# Solenoise_v6.net
KiCad netlist of a schematic drawn in EAGLE
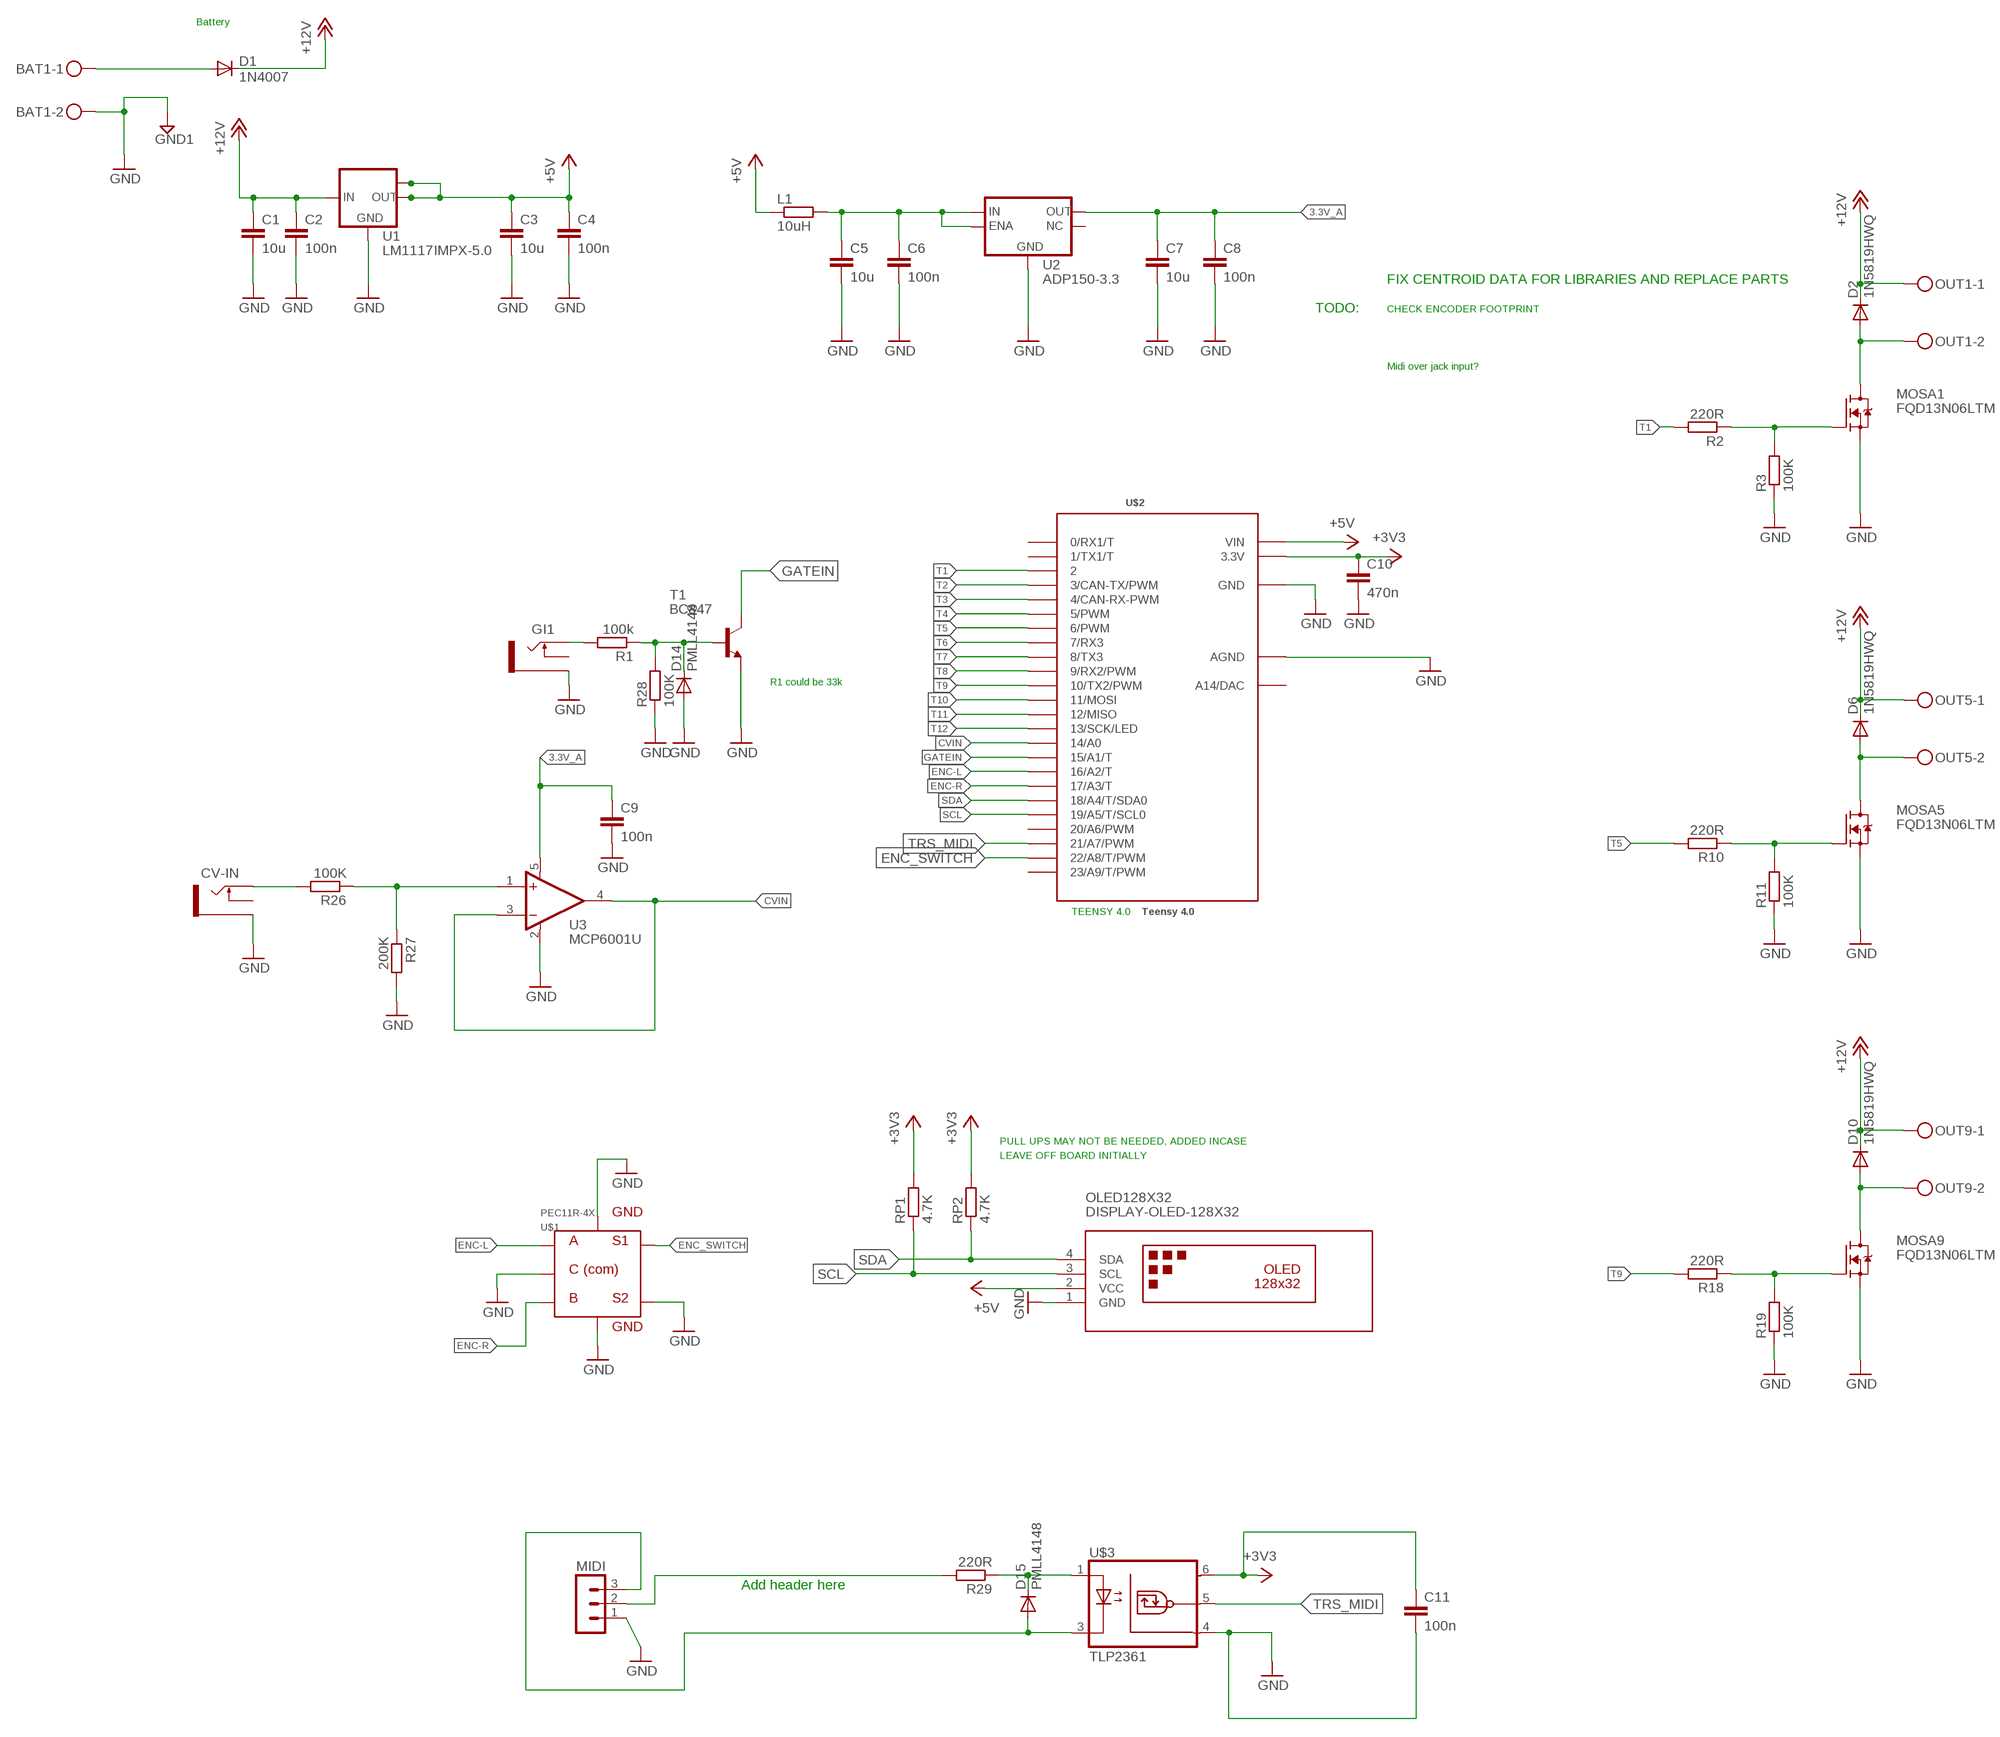
[diagram p0: schematic, sheet 1, part 1 of 2]
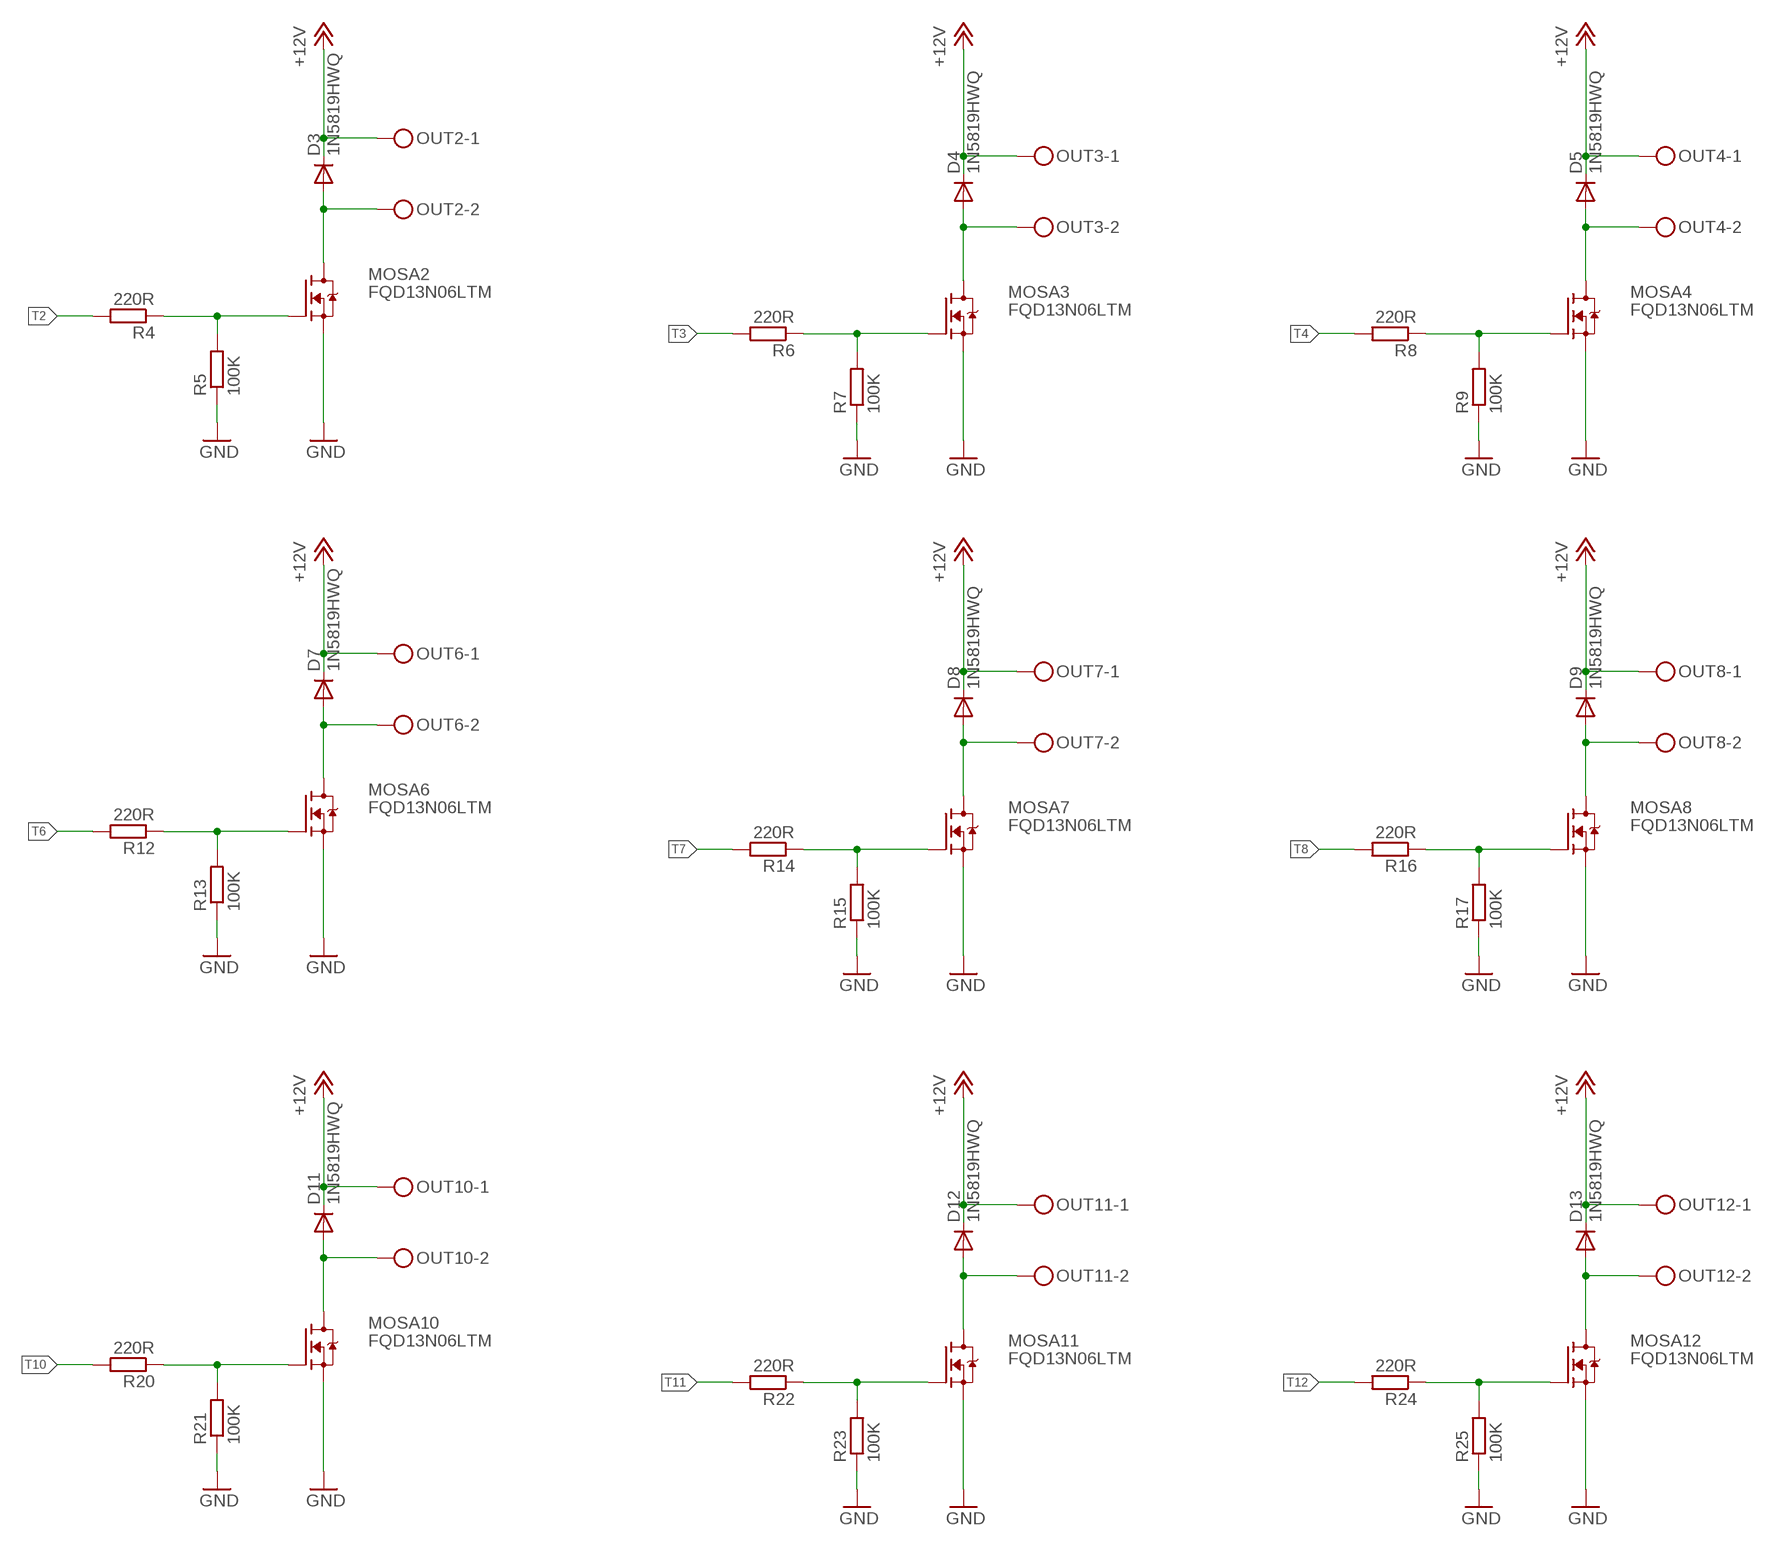
[diagram p1: schematic, sheet 1, part 2 of 2]

(export (version "E")
  (design (tool "Eeschema 10.0.6"))
  (components
    (comp (ref "BAT1")
      (value "MKDSN1,5/2-5,08")
      (footprint "eagle-import:MKDSN1,5_2-5,08")
      (fields (field (name "MPN") "MKDSN 1,5/2-5.08"))
      (libsource (lib "eagle-import") (part "MKDSN1,5/2-5,08"))
    )
    (comp (ref "C1")
      (value "10u")
      (footprint "eagle-import:C1206")
      (libsource (lib "eagle-import") (part "C-EUC1206"))
    )
    (comp (ref "C2")
      (value "100n")
      (footprint "eagle-import:C0805")
      (libsource (lib "eagle-import") (part "C-EUC0805"))
    )
    (comp (ref "C3")
      (value "10u")
      (footprint "eagle-import:C1206")
      (libsource (lib "eagle-import") (part "C-EUC1206"))
    )
    (comp (ref "C4")
      (value "100n")
      (footprint "eagle-import:C0805")
      (libsource (lib "eagle-import") (part "C-EUC0805"))
    )
    (comp (ref "C5")
      (value "10u")
      (footprint "eagle-import:C1206")
      (libsource (lib "eagle-import") (part "C-EUC1206"))
    )
    (comp (ref "C6")
      (value "100n")
      (footprint "eagle-import:C0805")
      (libsource (lib "eagle-import") (part "C-EUC0805"))
    )
    (comp (ref "C7")
      (value "10u")
      (footprint "eagle-import:C1206")
      (libsource (lib "eagle-import") (part "C-EUC1206"))
    )
    (comp (ref "C8")
      (value "100n")
      (footprint "eagle-import:C0805")
      (libsource (lib "eagle-import") (part "C-EUC0805"))
    )
    (comp (ref "C9")
      (value "100n")
      (footprint "eagle-import:C0805")
      (libsource (lib "eagle-import") (part "C-EUC0805"))
    )
    (comp (ref "C10")
      (value "470n")
      (footprint "eagle-import:C0805")
      (libsource (lib "eagle-import") (part "C-EUC0805"))
    )
    (comp (ref "C11")
      (value "100n")
      (footprint "eagle-import:C0805")
      (libsource (lib "eagle-import") (part "C-EUC0805"))
    )
    (comp (ref "CV-IN")
      (value "THONKICONNNEW")
      (footprint "eagle-import:WQP-PJ301M-12_JACK")
      (libsource (lib "eagle-import") (part "THONKICONNNEW"))
    )
    (comp (ref "D1")
      (value "1N4007")
      (footprint "eagle-import:DO41-10")
      (libsource (lib "eagle-import") (part "1N4004"))
    )
    (comp (ref "D2")
      (value "1N5819HWQ")
      (footprint "eagle-import:SOD123")
      (libsource (lib "eagle-import") (part "MBR0520LT"))
    )
    (comp (ref "D3")
      (value "1N5819HWQ")
      (footprint "eagle-import:SOD123")
      (libsource (lib "eagle-import") (part "MBR0520LT"))
    )
    (comp (ref "D4")
      (value "1N5819HWQ")
      (footprint "eagle-import:SOD123")
      (libsource (lib "eagle-import") (part "MBR0520LT"))
    )
    (comp (ref "D5")
      (value "1N5819HWQ")
      (footprint "eagle-import:SOD123")
      (libsource (lib "eagle-import") (part "MBR0520LT"))
    )
    (comp (ref "D6")
      (value "1N5819HWQ")
      (footprint "eagle-import:SOD123")
      (libsource (lib "eagle-import") (part "MBR0520LT"))
    )
    (comp (ref "D7")
      (value "1N5819HWQ")
      (footprint "eagle-import:SOD123")
      (libsource (lib "eagle-import") (part "MBR0520LT"))
    )
    (comp (ref "D8")
      (value "1N5819HWQ")
      (footprint "eagle-import:SOD123")
      (libsource (lib "eagle-import") (part "MBR0520LT"))
    )
    (comp (ref "D9")
      (value "1N5819HWQ")
      (footprint "eagle-import:SOD123")
      (libsource (lib "eagle-import") (part "MBR0520LT"))
    )
    (comp (ref "D10")
      (value "1N5819HWQ")
      (footprint "eagle-import:SOD123")
      (libsource (lib "eagle-import") (part "MBR0520LT"))
    )
    (comp (ref "D11")
      (value "1N5819HWQ")
      (footprint "eagle-import:SOD123")
      (libsource (lib "eagle-import") (part "MBR0520LT"))
    )
    (comp (ref "D12")
      (value "1N5819HWQ")
      (footprint "eagle-import:SOD123")
      (libsource (lib "eagle-import") (part "MBR0520LT"))
    )
    (comp (ref "D13")
      (value "1N5819HWQ")
      (footprint "eagle-import:SOD123")
      (libsource (lib "eagle-import") (part "MBR0520LT"))
    )
    (comp (ref "D14")
      (value "PMLL4148")
      (footprint "eagle-import:SOD80C")
      (libsource (lib "eagle-import") (part "PMLL4150"))
    )
    (comp (ref "D15")
      (value "PMLL4148")
      (footprint "eagle-import:SOD80C")
      (libsource (lib "eagle-import") (part "PMLL4150"))
    )
    (comp (ref "GI1")
      (value "THONKICONNNEW")
      (footprint "eagle-import:WQP-PJ301M-12_JACK")
      (libsource (lib "eagle-import") (part "THONKICONNNEW"))
    )
    (comp (ref "L1")
      (value "10uH")
      (footprint "eagle-import:R0805")
      (libsource (lib "eagle-import") (part "R-EU_R0805"))
    )
    (comp (ref "MIDI")
      (value "MA03-1")
      (footprint "eagle-import:MA03-1")
      (libsource (lib "eagle-import") (part "MA03-1"))
    )
    (comp (ref "MOSA1")
      (value "FQD13N06LTM")
      (footprint "eagle-import:FQD13N06LTM")
      (libsource (lib "eagle-import") (part "FQD13N06LTM"))
    )
    (comp (ref "MOSA2")
      (value "FQD13N06LTM")
      (footprint "eagle-import:FQD13N06LTM")
      (libsource (lib "eagle-import") (part "FQD13N06LTM"))
    )
    (comp (ref "MOSA3")
      (value "FQD13N06LTM")
      (footprint "eagle-import:FQD13N06LTM")
      (libsource (lib "eagle-import") (part "FQD13N06LTM"))
    )
    (comp (ref "MOSA4")
      (value "FQD13N06LTM")
      (footprint "eagle-import:FQD13N06LTM")
      (libsource (lib "eagle-import") (part "FQD13N06LTM"))
    )
    (comp (ref "MOSA5")
      (value "FQD13N06LTM")
      (footprint "eagle-import:FQD13N06LTM")
      (libsource (lib "eagle-import") (part "FQD13N06LTM"))
    )
    (comp (ref "MOSA6")
      (value "FQD13N06LTM")
      (footprint "eagle-import:FQD13N06LTM")
      (libsource (lib "eagle-import") (part "FQD13N06LTM"))
    )
    (comp (ref "MOSA7")
      (value "FQD13N06LTM")
      (footprint "eagle-import:FQD13N06LTM")
      (libsource (lib "eagle-import") (part "FQD13N06LTM"))
    )
    (comp (ref "MOSA8")
      (value "FQD13N06LTM")
      (footprint "eagle-import:FQD13N06LTM")
      (libsource (lib "eagle-import") (part "FQD13N06LTM"))
    )
    (comp (ref "MOSA9")
      (value "FQD13N06LTM")
      (footprint "eagle-import:FQD13N06LTM")
      (libsource (lib "eagle-import") (part "FQD13N06LTM"))
    )
    (comp (ref "MOSA10")
      (value "FQD13N06LTM")
      (footprint "eagle-import:FQD13N06LTM")
      (libsource (lib "eagle-import") (part "FQD13N06LTM"))
    )
    (comp (ref "MOSA11")
      (value "FQD13N06LTM")
      (footprint "eagle-import:FQD13N06LTM")
      (libsource (lib "eagle-import") (part "FQD13N06LTM"))
    )
    (comp (ref "MOSA12")
      (value "FQD13N06LTM")
      (footprint "eagle-import:FQD13N06LTM")
      (libsource (lib "eagle-import") (part "FQD13N06LTM"))
    )
    (comp (ref "OLED128X32")
      (value "DISPLAY-OLED-128X32")
      (footprint "eagle-import:DISPLAY-OLED-128X32")
      (libsource (lib "eagle-import") (part "DISPLAY-OLED-128X32"))
    )
    (comp (ref "OUT1")
      (value "MKDSN1,5/2-5,08")
      (footprint "eagle-import:MKDSN1,5_2-5,08")
      (fields (field (name "MPN") "MKDSN 1,5/2-5.08"))
      (libsource (lib "eagle-import") (part "MKDSN1,5/2-5,08"))
    )
    (comp (ref "OUT2")
      (value "MKDSN1,5/2-5,08")
      (footprint "eagle-import:MKDSN1,5_2-5,08")
      (fields (field (name "MPN") "MKDSN 1,5/2-5.08"))
      (libsource (lib "eagle-import") (part "MKDSN1,5/2-5,08"))
    )
    (comp (ref "OUT3")
      (value "MKDSN1,5/2-5,08")
      (footprint "eagle-import:MKDSN1,5_2-5,08")
      (fields (field (name "MPN") "MKDSN 1,5/2-5.08"))
      (libsource (lib "eagle-import") (part "MKDSN1,5/2-5,08"))
    )
    (comp (ref "OUT4")
      (value "MKDSN1,5/2-5,08")
      (footprint "eagle-import:MKDSN1,5_2-5,08")
      (fields (field (name "MPN") "MKDSN 1,5/2-5.08"))
      (libsource (lib "eagle-import") (part "MKDSN1,5/2-5,08"))
    )
    (comp (ref "OUT5")
      (value "MKDSN1,5/2-5,08")
      (footprint "eagle-import:MKDSN1,5_2-5,08")
      (fields (field (name "MPN") "MKDSN 1,5/2-5.08"))
      (libsource (lib "eagle-import") (part "MKDSN1,5/2-5,08"))
    )
    (comp (ref "OUT6")
      (value "MKDSN1,5/2-5,08")
      (footprint "eagle-import:MKDSN1,5_2-5,08")
      (fields (field (name "MPN") "MKDSN 1,5/2-5.08"))
      (libsource (lib "eagle-import") (part "MKDSN1,5/2-5,08"))
    )
    (comp (ref "OUT7")
      (value "MKDSN1,5/2-5,08")
      (footprint "eagle-import:MKDSN1,5_2-5,08")
      (fields (field (name "MPN") "MKDSN 1,5/2-5.08"))
      (libsource (lib "eagle-import") (part "MKDSN1,5/2-5,08"))
    )
    (comp (ref "OUT8")
      (value "MKDSN1,5/2-5,08")
      (footprint "eagle-import:MKDSN1,5_2-5,08")
      (fields (field (name "MPN") "MKDSN 1,5/2-5.08"))
      (libsource (lib "eagle-import") (part "MKDSN1,5/2-5,08"))
    )
    (comp (ref "OUT9")
      (value "MKDSN1,5/2-5,08")
      (footprint "eagle-import:MKDSN1,5_2-5,08")
      (fields (field (name "MPN") "MKDSN 1,5/2-5.08"))
      (libsource (lib "eagle-import") (part "MKDSN1,5/2-5,08"))
    )
    (comp (ref "OUT10")
      (value "MKDSN1,5/2-5,08")
      (footprint "eagle-import:MKDSN1,5_2-5,08")
      (fields (field (name "MPN") "MKDSN 1,5/2-5.08"))
      (libsource (lib "eagle-import") (part "MKDSN1,5/2-5,08"))
    )
    (comp (ref "OUT11")
      (value "MKDSN1,5/2-5,08")
      (footprint "eagle-import:MKDSN1,5_2-5,08")
      (fields (field (name "MPN") "MKDSN 1,5/2-5.08"))
      (libsource (lib "eagle-import") (part "MKDSN1,5/2-5,08"))
    )
    (comp (ref "OUT12")
      (value "MKDSN1,5/2-5,08")
      (footprint "eagle-import:MKDSN1,5_2-5,08")
      (fields (field (name "MPN") "MKDSN 1,5/2-5.08"))
      (libsource (lib "eagle-import") (part "MKDSN1,5/2-5,08"))
    )
    (comp (ref "R1")
      (value "100k")
      (footprint "eagle-import:R0805")
      (libsource (lib "eagle-import") (part "R-EU_R0805"))
    )
    (comp (ref "R2")
      (value "220R")
      (footprint "eagle-import:R0805")
      (libsource (lib "eagle-import") (part "R-EU_R0805"))
    )
    (comp (ref "R3")
      (value "100K")
      (footprint "eagle-import:R0805")
      (libsource (lib "eagle-import") (part "R-EU_R0805"))
    )
    (comp (ref "R4")
      (value "220R")
      (footprint "eagle-import:R0805")
      (libsource (lib "eagle-import") (part "R-EU_R0805"))
    )
    (comp (ref "R5")
      (value "100K")
      (footprint "eagle-import:R0805")
      (libsource (lib "eagle-import") (part "R-EU_R0805"))
    )
    (comp (ref "R6")
      (value "220R")
      (footprint "eagle-import:R0805")
      (libsource (lib "eagle-import") (part "R-EU_R0805"))
    )
    (comp (ref "R7")
      (value "100K")
      (footprint "eagle-import:R0805")
      (libsource (lib "eagle-import") (part "R-EU_R0805"))
    )
    (comp (ref "R8")
      (value "220R")
      (footprint "eagle-import:R0805")
      (libsource (lib "eagle-import") (part "R-EU_R0805"))
    )
    (comp (ref "R9")
      (value "100K")
      (footprint "eagle-import:R0805")
      (libsource (lib "eagle-import") (part "R-EU_R0805"))
    )
    (comp (ref "R10")
      (value "220R")
      (footprint "eagle-import:R0805")
      (libsource (lib "eagle-import") (part "R-EU_R0805"))
    )
    (comp (ref "R11")
      (value "100K")
      (footprint "eagle-import:R0805")
      (libsource (lib "eagle-import") (part "R-EU_R0805"))
    )
    (comp (ref "R12")
      (value "220R")
      (footprint "eagle-import:R0805")
      (libsource (lib "eagle-import") (part "R-EU_R0805"))
    )
    (comp (ref "R13")
      (value "100K")
      (footprint "eagle-import:R0805")
      (libsource (lib "eagle-import") (part "R-EU_R0805"))
    )
    (comp (ref "R14")
      (value "220R")
      (footprint "eagle-import:R0805")
      (libsource (lib "eagle-import") (part "R-EU_R0805"))
    )
    (comp (ref "R15")
      (value "100K")
      (footprint "eagle-import:R0805")
      (libsource (lib "eagle-import") (part "R-EU_R0805"))
    )
    (comp (ref "R16")
      (value "220R")
      (footprint "eagle-import:R0805")
      (libsource (lib "eagle-import") (part "R-EU_R0805"))
    )
    (comp (ref "R17")
      (value "100K")
      (footprint "eagle-import:R0805")
      (libsource (lib "eagle-import") (part "R-EU_R0805"))
    )
    (comp (ref "R18")
      (value "220R")
      (footprint "eagle-import:R0805")
      (libsource (lib "eagle-import") (part "R-EU_R0805"))
    )
    (comp (ref "R19")
      (value "100K")
      (footprint "eagle-import:R0805")
      (libsource (lib "eagle-import") (part "R-EU_R0805"))
    )
    (comp (ref "R20")
      (value "220R")
      (footprint "eagle-import:R0805")
      (libsource (lib "eagle-import") (part "R-EU_R0805"))
    )
    (comp (ref "R21")
      (value "100K")
      (footprint "eagle-import:R0805")
      (libsource (lib "eagle-import") (part "R-EU_R0805"))
    )
    (comp (ref "R22")
      (value "220R")
      (footprint "eagle-import:R0805")
      (libsource (lib "eagle-import") (part "R-EU_R0805"))
    )
    (comp (ref "R23")
      (value "100K")
      (footprint "eagle-import:R0805")
      (libsource (lib "eagle-import") (part "R-EU_R0805"))
    )
    (comp (ref "R24")
      (value "220R")
      (footprint "eagle-import:R0805")
      (libsource (lib "eagle-import") (part "R-EU_R0805"))
    )
    (comp (ref "R25")
      (value "100K")
      (footprint "eagle-import:R0805")
      (libsource (lib "eagle-import") (part "R-EU_R0805"))
    )
    (comp (ref "R26")
      (value "100K")
      (footprint "eagle-import:R0805")
      (libsource (lib "eagle-import") (part "R-EU_R0805"))
    )
    (comp (ref "R27")
      (value "200K")
      (footprint "eagle-import:R0805")
      (libsource (lib "eagle-import") (part "R-EU_R0805"))
    )
    (comp (ref "R28")
      (value "100K")
      (footprint "eagle-import:R0805")
      (libsource (lib "eagle-import") (part "R-EU_R0805"))
    )
    (comp (ref "R29")
      (value "220R")
      (footprint "eagle-import:R0805")
      (libsource (lib "eagle-import") (part "R-EU_R0805"))
    )
    (comp (ref "RP1")
      (value "4.7K")
      (footprint "eagle-import:R0805")
      (libsource (lib "eagle-import") (part "R-EU_R0805"))
    )
    (comp (ref "RP2")
      (value "4.7K")
      (footprint "eagle-import:R0805")
      (libsource (lib "eagle-import") (part "R-EU_R0805"))
    )
    (comp (ref "T1")
      (value "BC847")
      (footprint "eagle-import:SOT23")
      (libsource (lib "eagle-import") (part "BC847"))
    )
    (comp (ref "U$1")
      (value "PEC11R-4X")
      (footprint "eagle-import:ENC")
      (libsource (lib "eagle-import") (part "PEC11R-4X"))
    )
    (comp (ref "U$2")
      (value "Teensy 4.0")
      (footprint "eagle-import:TEENSY_3.1_DAC")
      (libsource (lib "eagle-import") (part "TEENSY_3.1_DAC"))
    )
    (comp (ref "U$3")
      (value "TLP2361")
      (footprint "eagle-import:TLP2361")
      (libsource (lib "eagle-import") (part "TLP2361"))
    )
    (comp (ref "U1")
      (value "LM1117IMPX-5.0")
      (footprint "eagle-import:SOT223")
      (libsource (lib "eagle-import") (part "LM1117IMPX-5.0"))
    )
    (comp (ref "U2")
      (value "ADP150-3.3")
      (footprint "eagle-import:SOT23-5")
      (libsource (lib "eagle-import") (part "ADP150-3.3"))
    )
    (comp (ref "U3")
      (value "MCP6001U")
      (footprint "eagle-import:MCP6001")
      (libsource (lib "eagle-import") (part "MCP6001U"))
    )
  )
  (nets
    (net (code "1") (name "+3V3") (class "Default")
      (node (ref "C10") (pin "1") (pinfunction "1_1") (pintype "passive"))
      (node (ref "C11") (pin "1") (pinfunction "1_1") (pintype "passive"))
      (node (ref "RP1") (pin "2") (pinfunction "2_2") (pintype "passive"))
      (node (ref "RP2") (pin "2") (pinfunction "2_2") (pintype "passive"))
      (node (ref "U$2") (pin "3.3V") (pinfunction "3.3V_3.3V") (pintype "power_in"))
      (node (ref "U$3") (pin "6") (pinfunction "VCC_6") (pintype "passive"))
    )
    (net (code "2") (name "+5V") (class "Default")
      (node (ref "C3") (pin "1") (pinfunction "1_1") (pintype "passive"))
      (node (ref "C4") (pin "1") (pinfunction "1_1") (pintype "passive"))
      (node (ref "L1") (pin "1") (pinfunction "1_1") (pintype "passive"))
      (node (ref "OLED128X32") (pin "2") (pinfunction "VCC_2") (pintype "power_in"))
      (node (ref "U$2") (pin "VIN") (pinfunction "VIN_VIN") (pintype "power_in"))
      (node (ref "U1") (pin "2") (pinfunction "OUT_2") (pintype "passive"))
      (node (ref "U1") (pin "TAB") (pinfunction "OUT1_TAB") (pintype "passive"))
    )
    (net (code "3") (name "+12V") (class "Default")
      (node (ref "C1") (pin "1") (pinfunction "1_1") (pintype "passive"))
      (node (ref "C2") (pin "1") (pinfunction "1_1") (pintype "passive"))
      (node (ref "D1") (pin "C") (pinfunction "C_C") (pintype "passive"))
      (node (ref "D10") (pin "C") (pinfunction "C_C") (pintype "passive"))
      (node (ref "D11") (pin "C") (pinfunction "C_C") (pintype "passive"))
      (node (ref "D12") (pin "C") (pinfunction "C_C") (pintype "passive"))
      (node (ref "D13") (pin "C") (pinfunction "C_C") (pintype "passive"))
      (node (ref "D2") (pin "C") (pinfunction "C_C") (pintype "passive"))
      (node (ref "D3") (pin "C") (pinfunction "C_C") (pintype "passive"))
      (node (ref "D4") (pin "C") (pinfunction "C_C") (pintype "passive"))
      (node (ref "D5") (pin "C") (pinfunction "C_C") (pintype "passive"))
      (node (ref "D6") (pin "C") (pinfunction "C_C") (pintype "passive"))
      (node (ref "D7") (pin "C") (pinfunction "C_C") (pintype "passive"))
      (node (ref "D8") (pin "C") (pinfunction "C_C") (pintype "passive"))
      (node (ref "D9") (pin "C") (pinfunction "C_C") (pintype "passive"))
      (node (ref "OUT1") (pin "1") (pinfunction "KL_1") (pintype "passive"))
      (node (ref "OUT10") (pin "1") (pinfunction "KL_1") (pintype "passive"))
      (node (ref "OUT11") (pin "1") (pinfunction "KL_1") (pintype "passive"))
      (node (ref "OUT12") (pin "1") (pinfunction "KL_1") (pintype "passive"))
      (node (ref "OUT2") (pin "1") (pinfunction "KL_1") (pintype "passive"))
      (node (ref "OUT3") (pin "1") (pinfunction "KL_1") (pintype "passive"))
      (node (ref "OUT4") (pin "1") (pinfunction "KL_1") (pintype "passive"))
      (node (ref "OUT5") (pin "1") (pinfunction "KL_1") (pintype "passive"))
      (node (ref "OUT6") (pin "1") (pinfunction "KL_1") (pintype "passive"))
      (node (ref "OUT7") (pin "1") (pinfunction "KL_1") (pintype "passive"))
      (node (ref "OUT8") (pin "1") (pinfunction "KL_1") (pintype "passive"))
      (node (ref "OUT9") (pin "1") (pinfunction "KL_1") (pintype "passive"))
      (node (ref "U1") (pin "3") (pinfunction "IN_3") (pintype "input"))
    )
    (net (code "4") (name "3.3V_A") (class "Default")
      (node (ref "C7") (pin "1") (pinfunction "1_1") (pintype "passive"))
      (node (ref "C8") (pin "1") (pinfunction "1_1") (pintype "passive"))
      (node (ref "C9") (pin "1") (pinfunction "1_1") (pintype "passive"))
      (node (ref "U2") (pin "OUT") (pinfunction "VOUT_OUT") (pintype "passive"))
      (node (ref "U3") (pin "5") (pinfunction "V+_5") (pintype "power_in"))
    )
    (net (code "5") (name "CVIN") (class "Default")
      (node (ref "U$2") (pin "14/A0") (pinfunction "14/A0_14/A0") (pintype "bidirectional"))
      (node (ref "U3") (pin "3") (pinfunction "-IN_3") (pintype "input"))
      (node (ref "U3") (pin "4") (pinfunction "OUT_4") (pintype "output"))
    )
    (net (code "6") (name "ENC-L") (class "Default")
      (node (ref "U$1") (pin "A") (pinfunction "A_A") (pintype "passive"))
      (node (ref "U$2") (pin "16/A2") (pinfunction "16/A2/T_16/A2") (pintype "bidirectional"))
    )
    (net (code "7") (name "ENC-R") (class "Default")
      (node (ref "U$1") (pin "B") (pinfunction "B_B") (pintype "passive"))
      (node (ref "U$2") (pin "17/A3") (pinfunction "17/A3/T_17/A3") (pintype "bidirectional"))
    )
    (net (code "8") (name "ENC_SWITCH") (class "Default")
      (node (ref "U$1") (pin "1") (pinfunction "SW1_1") (pintype "passive"))
      (node (ref "U$2") (pin "22/A8") (pinfunction "22/A8/T/PWM_22/A8") (pintype "bidirectional"))
    )
    (net (code "9") (name "GATEIN") (class "Default")
      (node (ref "T1") (pin "3") (pinfunction "C_3") (pintype "passive"))
      (node (ref "U$2") (pin "15/A1") (pinfunction "15/A1/T_15/A1") (pintype "bidirectional"))
    )
    (net (code "10") (name "GND") (class "Default")
      (node (ref "BAT1") (pin "2") (pinfunction "KL_2") (pintype "passive"))
      (node (ref "C1") (pin "2") (pinfunction "2_2") (pintype "passive"))
      (node (ref "C10") (pin "2") (pinfunction "2_2") (pintype "passive"))
      (node (ref "C11") (pin "2") (pinfunction "2_2") (pintype "passive"))
      (node (ref "C2") (pin "2") (pinfunction "2_2") (pintype "passive"))
      (node (ref "C3") (pin "2") (pinfunction "2_2") (pintype "passive"))
      (node (ref "C4") (pin "2") (pinfunction "2_2") (pintype "passive"))
      (node (ref "C5") (pin "2") (pinfunction "2_2") (pintype "passive"))
      (node (ref "C6") (pin "2") (pinfunction "2_2") (pintype "passive"))
      (node (ref "C7") (pin "2") (pinfunction "2_2") (pintype "passive"))
      (node (ref "C8") (pin "2") (pinfunction "2_2") (pintype "passive"))
      (node (ref "C9") (pin "2") (pinfunction "2_2") (pintype "passive"))
      (node (ref "CV-IN") (pin "P$3_SLEEVE") (pinfunction "SLEEVE_P$3_SLEEVE") (pintype "passive"))
      (node (ref "D14") (pin "A") (pinfunction "A_A") (pintype "passive"))
      (node (ref "GI1") (pin "P$3_SLEEVE") (pinfunction "SLEEVE_P$3_SLEEVE") (pintype "passive"))
      (node (ref "MIDI") (pin "1") (pinfunction "1_1") (pintype "passive"))
      (node (ref "MOSA1") (pin "2") (pinfunction "S_2") (pintype "passive"))
      (node (ref "MOSA10") (pin "2") (pinfunction "S_2") (pintype "passive"))
      (node (ref "MOSA11") (pin "2") (pinfunction "S_2") (pintype "passive"))
      (node (ref "MOSA12") (pin "2") (pinfunction "S_2") (pintype "passive"))
      (node (ref "MOSA2") (pin "2") (pinfunction "S_2") (pintype "passive"))
      (node (ref "MOSA3") (pin "2") (pinfunction "S_2") (pintype "passive"))
      (node (ref "MOSA4") (pin "2") (pinfunction "S_2") (pintype "passive"))
      (node (ref "MOSA5") (pin "2") (pinfunction "S_2") (pintype "passive"))
      (node (ref "MOSA6") (pin "2") (pinfunction "S_2") (pintype "passive"))
      (node (ref "MOSA7") (pin "2") (pinfunction "S_2") (pintype "passive"))
      (node (ref "MOSA8") (pin "2") (pinfunction "S_2") (pintype "passive"))
      (node (ref "MOSA9") (pin "2") (pinfunction "S_2") (pintype "passive"))
      (node (ref "OLED128X32") (pin "1") (pinfunction "GND_1") (pintype "power_in"))
      (node (ref "R11") (pin "1") (pinfunction "1_1") (pintype "passive"))
      (node (ref "R13") (pin "1") (pinfunction "1_1") (pintype "passive"))
      (node (ref "R15") (pin "1") (pinfunction "1_1") (pintype "passive"))
      (node (ref "R17") (pin "1") (pinfunction "1_1") (pintype "passive"))
      (node (ref "R19") (pin "1") (pinfunction "1_1") (pintype "passive"))
      (node (ref "R21") (pin "1") (pinfunction "1_1") (pintype "passive"))
      (node (ref "R23") (pin "1") (pinfunction "1_1") (pintype "passive"))
      (node (ref "R25") (pin "1") (pinfunction "1_1") (pintype "passive"))
      (node (ref "R27") (pin "2") (pinfunction "2_2") (pintype "passive"))
      (node (ref "R28") (pin "1") (pinfunction "1_1") (pintype "passive"))
      (node (ref "R3") (pin "1") (pinfunction "1_1") (pintype "passive"))
      (node (ref "R5") (pin "1") (pinfunction "1_1") (pintype "passive"))
      (node (ref "R7") (pin "1") (pinfunction "1_1") (pintype "passive"))
      (node (ref "R9") (pin "1") (pinfunction "1_1") (pintype "passive"))
      (node (ref "T1") (pin "2") (pinfunction "E_2") (pintype "passive"))
      (node (ref "U$1") (pin "2") (pinfunction "SW2_2") (pintype "passive"))
      (node (ref "U$1") (pin "C") (pinfunction "C_C") (pintype "passive"))
      (node (ref "U$1") (pin "GND1") (pinfunction "GND1_GND1") (pintype "passive"))
      (node (ref "U$1") (pin "GND2") (pinfunction "GND2_GND2") (pintype "passive"))
      (node (ref "U$2") (pin "AGND") (pinfunction "AGND_AGND") (pintype "power_in"))
      (node (ref "U$2") (pin "GND") (pinfunction "GND_GND") (pintype "power_in"))
      (node (ref "U$3") (pin "4") (pinfunction "GND_4") (pintype "passive"))
      (node (ref "U1") (pin "1") (pinfunction "GND_1") (pintype "input"))
      (node (ref "U2") (pin "GND") (pinfunction "GND_GND") (pintype "input"))
      (node (ref "U3") (pin "2") (pinfunction "V-_2") (pintype "power_in"))
    )
    (net (code "11") (name "Net-(BAT1A-KL)") (class "Default")
      (node (ref "BAT1") (pin "1") (pinfunction "KL_1") (pintype "passive"))
      (node (ref "D1") (pin "A") (pinfunction "A_A") (pintype "passive"))
    )
    (net (code "12") (name "Net-(CV-IN-TIP)") (class "Default")
      (node (ref "CV-IN") (pin "P$1_TIP") (pinfunction "TIP_P$1_TIP") (pintype "passive"))
      (node (ref "R26") (pin "2") (pinfunction "2_2") (pintype "passive"))
    )
    (net (code "13") (name "Net-(GI1-TIP)") (class "Default")
      (node (ref "GI1") (pin "P$1_TIP") (pinfunction "TIP_P$1_TIP") (pintype "passive"))
      (node (ref "R1") (pin "2") (pinfunction "2_2") (pintype "passive"))
    )
    (net (code "14") (name "Net-(MIDI-Pad2)") (class "Default")
      (node (ref "MIDI") (pin "2") (pinfunction "2_2") (pintype "passive"))
      (node (ref "R29") (pin "2") (pinfunction "2_2") (pintype "passive"))
    )
    (net (code "15") (name "Net-(MOSA1-D)") (class "Default")
      (node (ref "D2") (pin "A") (pinfunction "A_A") (pintype "passive"))
      (node (ref "MOSA1") (pin "3") (pinfunction "D_3") (pintype "passive"))
      (node (ref "OUT1") (pin "2") (pinfunction "KL_2") (pintype "passive"))
    )
    (net (code "16") (name "Net-(MOSA1-G)") (class "Default")
      (node (ref "MOSA1") (pin "1") (pinfunction "G_1") (pintype "passive"))
      (node (ref "R2") (pin "1") (pinfunction "1_1") (pintype "passive"))
      (node (ref "R3") (pin "2") (pinfunction "2_2") (pintype "passive"))
    )
    (net (code "17") (name "Net-(MOSA2-D)") (class "Default")
      (node (ref "D3") (pin "A") (pinfunction "A_A") (pintype "passive"))
      (node (ref "MOSA2") (pin "3") (pinfunction "D_3") (pintype "passive"))
      (node (ref "OUT2") (pin "2") (pinfunction "KL_2") (pintype "passive"))
    )
    (net (code "18") (name "Net-(MOSA2-G)") (class "Default")
      (node (ref "MOSA2") (pin "1") (pinfunction "G_1") (pintype "passive"))
      (node (ref "R4") (pin "1") (pinfunction "1_1") (pintype "passive"))
      (node (ref "R5") (pin "2") (pinfunction "2_2") (pintype "passive"))
    )
    (net (code "19") (name "Net-(MOSA3-D)") (class "Default")
      (node (ref "D4") (pin "A") (pinfunction "A_A") (pintype "passive"))
      (node (ref "MOSA3") (pin "3") (pinfunction "D_3") (pintype "passive"))
      (node (ref "OUT3") (pin "2") (pinfunction "KL_2") (pintype "passive"))
    )
    (net (code "20") (name "Net-(MOSA3-G)") (class "Default")
      (node (ref "MOSA3") (pin "1") (pinfunction "G_1") (pintype "passive"))
      (node (ref "R6") (pin "1") (pinfunction "1_1") (pintype "passive"))
      (node (ref "R7") (pin "2") (pinfunction "2_2") (pintype "passive"))
    )
    (net (code "21") (name "Net-(MOSA4-D)") (class "Default")
      (node (ref "D5") (pin "A") (pinfunction "A_A") (pintype "passive"))
      (node (ref "MOSA4") (pin "3") (pinfunction "D_3") (pintype "passive"))
      (node (ref "OUT4") (pin "2") (pinfunction "KL_2") (pintype "passive"))
    )
    (net (code "22") (name "Net-(MOSA4-G)") (class "Default")
      (node (ref "MOSA4") (pin "1") (pinfunction "G_1") (pintype "passive"))
      (node (ref "R8") (pin "1") (pinfunction "1_1") (pintype "passive"))
      (node (ref "R9") (pin "2") (pinfunction "2_2") (pintype "passive"))
    )
    (net (code "23") (name "Net-(MOSA5-D)") (class "Default")
      (node (ref "D6") (pin "A") (pinfunction "A_A") (pintype "passive"))
      (node (ref "MOSA5") (pin "3") (pinfunction "D_3") (pintype "passive"))
      (node (ref "OUT5") (pin "2") (pinfunction "KL_2") (pintype "passive"))
    )
    (net (code "24") (name "Net-(MOSA5-G)") (class "Default")
      (node (ref "MOSA5") (pin "1") (pinfunction "G_1") (pintype "passive"))
      (node (ref "R10") (pin "1") (pinfunction "1_1") (pintype "passive"))
      (node (ref "R11") (pin "2") (pinfunction "2_2") (pintype "passive"))
    )
    (net (code "25") (name "Net-(MOSA6-D)") (class "Default")
      (node (ref "D7") (pin "A") (pinfunction "A_A") (pintype "passive"))
      (node (ref "MOSA6") (pin "3") (pinfunction "D_3") (pintype "passive"))
      (node (ref "OUT6") (pin "2") (pinfunction "KL_2") (pintype "passive"))
    )
    (net (code "26") (name "Net-(MOSA6-G)") (class "Default")
      (node (ref "MOSA6") (pin "1") (pinfunction "G_1") (pintype "passive"))
      (node (ref "R12") (pin "1") (pinfunction "1_1") (pintype "passive"))
      (node (ref "R13") (pin "2") (pinfunction "2_2") (pintype "passive"))
    )
    (net (code "27") (name "Net-(MOSA7-D)") (class "Default")
      (node (ref "D8") (pin "A") (pinfunction "A_A") (pintype "passive"))
      (node (ref "MOSA7") (pin "3") (pinfunction "D_3") (pintype "passive"))
      (node (ref "OUT7") (pin "2") (pinfunction "KL_2") (pintype "passive"))
    )
    (net (code "28") (name "Net-(MOSA7-G)") (class "Default")
      (node (ref "MOSA7") (pin "1") (pinfunction "G_1") (pintype "passive"))
      (node (ref "R14") (pin "1") (pinfunction "1_1") (pintype "passive"))
      (node (ref "R15") (pin "2") (pinfunction "2_2") (pintype "passive"))
    )
    (net (code "29") (name "Net-(MOSA8-D)") (class "Default")
      (node (ref "D9") (pin "A") (pinfunction "A_A") (pintype "passive"))
      (node (ref "MOSA8") (pin "3") (pinfunction "D_3") (pintype "passive"))
      (node (ref "OUT8") (pin "2") (pinfunction "KL_2") (pintype "passive"))
    )
    (net (code "30") (name "Net-(MOSA8-G)") (class "Default")
      (node (ref "MOSA8") (pin "1") (pinfunction "G_1") (pintype "passive"))
      (node (ref "R16") (pin "1") (pinfunction "1_1") (pintype "passive"))
      (node (ref "R17") (pin "2") (pinfunction "2_2") (pintype "passive"))
    )
    (net (code "31") (name "Net-(MOSA9-D)") (class "Default")
      (node (ref "D10") (pin "A") (pinfunction "A_A") (pintype "passive"))
      (node (ref "MOSA9") (pin "3") (pinfunction "D_3") (pintype "passive"))
      (node (ref "OUT9") (pin "2") (pinfunction "KL_2") (pintype "passive"))
    )
    (net (code "32") (name "Net-(MOSA9-G)") (class "Default")
      (node (ref "MOSA9") (pin "1") (pinfunction "G_1") (pintype "passive"))
      (node (ref "R18") (pin "1") (pinfunction "1_1") (pintype "passive"))
      (node (ref "R19") (pin "2") (pinfunction "2_2") (pintype "passive"))
    )
    (net (code "33") (name "Net-(MOSA10-D)") (class "Default")
      (node (ref "D11") (pin "A") (pinfunction "A_A") (pintype "passive"))
      (node (ref "MOSA10") (pin "3") (pinfunction "D_3") (pintype "passive"))
      (node (ref "OUT10") (pin "2") (pinfunction "KL_2") (pintype "passive"))
    )
    (net (code "34") (name "Net-(MOSA10-G)") (class "Default")
      (node (ref "MOSA10") (pin "1") (pinfunction "G_1") (pintype "passive"))
      (node (ref "R20") (pin "1") (pinfunction "1_1") (pintype "passive"))
      (node (ref "R21") (pin "2") (pinfunction "2_2") (pintype "passive"))
    )
    (net (code "35") (name "Net-(MOSA11-D)") (class "Default")
      (node (ref "D12") (pin "A") (pinfunction "A_A") (pintype "passive"))
      (node (ref "MOSA11") (pin "3") (pinfunction "D_3") (pintype "passive"))
      (node (ref "OUT11") (pin "2") (pinfunction "KL_2") (pintype "passive"))
    )
    (net (code "36") (name "Net-(MOSA11-G)") (class "Default")
      (node (ref "MOSA11") (pin "1") (pinfunction "G_1") (pintype "passive"))
      (node (ref "R22") (pin "1") (pinfunction "1_1") (pintype "passive"))
      (node (ref "R23") (pin "2") (pinfunction "2_2") (pintype "passive"))
    )
    (net (code "37") (name "Net-(MOSA12-D)") (class "Default")
      (node (ref "D13") (pin "A") (pinfunction "A_A") (pintype "passive"))
      (node (ref "MOSA12") (pin "3") (pinfunction "D_3") (pintype "passive"))
      (node (ref "OUT12") (pin "2") (pinfunction "KL_2") (pintype "passive"))
    )
    (net (code "38") (name "Net-(MOSA12-G)") (class "Default")
      (node (ref "MOSA12") (pin "1") (pinfunction "G_1") (pintype "passive"))
      (node (ref "R24") (pin "1") (pinfunction "1_1") (pintype "passive"))
      (node (ref "R25") (pin "2") (pinfunction "2_2") (pintype "passive"))
    )
    (net (code "39") (name "Net-(T1-B)") (class "Default")
      (node (ref "D14") (pin "C") (pinfunction "C_C") (pintype "passive"))
      (node (ref "R1") (pin "1") (pinfunction "1_1") (pintype "passive"))
      (node (ref "R28") (pin "2") (pinfunction "2_2") (pintype "passive"))
      (node (ref "T1") (pin "1") (pinfunction "B_1") (pintype "passive"))
    )
    (net (code "40") (name "Net-(U$3-A)") (class "Default")
      (node (ref "D15") (pin "C") (pinfunction "C_C") (pintype "passive"))
      (node (ref "R29") (pin "1") (pinfunction "1_1") (pintype "passive"))
      (node (ref "U$3") (pin "1") (pinfunction "A_1") (pintype "passive"))
    )
    (net (code "41") (name "Net-(U$3-C)") (class "Default")
      (node (ref "D15") (pin "A") (pinfunction "A_A") (pintype "passive"))
      (node (ref "MIDI") (pin "3") (pinfunction "3_3") (pintype "passive"))
      (node (ref "U$3") (pin "3") (pinfunction "C_3") (pintype "passive"))
    )
    (net (code "42") (name "Net-(U2-ENA)") (class "Default")
      (node (ref "C5") (pin "1") (pinfunction "1_1") (pintype "passive"))
      (node (ref "C6") (pin "1") (pinfunction "1_1") (pintype "passive"))
      (node (ref "L1") (pin "2") (pinfunction "2_2") (pintype "passive"))
      (node (ref "U2") (pin "EN") (pinfunction "ENA_EN") (pintype "input"))
      (node (ref "U2") (pin "VIN") (pinfunction "IN_VIN") (pintype "input"))
    )
    (net (code "43") (name "Net-(U3-+IN)") (class "Default")
      (node (ref "R26") (pin "1") (pinfunction "1_1") (pintype "passive"))
      (node (ref "R27") (pin "1") (pinfunction "1_1") (pintype "passive"))
      (node (ref "U3") (pin "1") (pinfunction "+IN_1") (pintype "input"))
    )
    (net (code "44") (name "SCL") (class "Default")
      (node (ref "OLED128X32") (pin "3") (pinfunction "SCL_3") (pintype "bidirectional"))
      (node (ref "RP1") (pin "1") (pinfunction "1_1") (pintype "passive"))
      (node (ref "U$2") (pin "19/A5") (pinfunction "19/A5/T/SCL0_19/A5") (pintype "bidirectional"))
    )
    (net (code "45") (name "SDA") (class "Default")
      (node (ref "OLED128X32") (pin "4") (pinfunction "SDA_4") (pintype "bidirectional"))
      (node (ref "RP2") (pin "1") (pinfunction "1_1") (pintype "passive"))
      (node (ref "U$2") (pin "18/A4") (pinfunction "18/A4/T/SDA0_18/A4") (pintype "bidirectional"))
    )
    (net (code "46") (name "T1") (class "Default")
      (node (ref "R2") (pin "2") (pinfunction "2_2") (pintype "passive"))
      (node (ref "U$2") (pin "2") (pinfunction "2_2") (pintype "bidirectional"))
    )
    (net (code "47") (name "T2") (class "Default")
      (node (ref "R4") (pin "2") (pinfunction "2_2") (pintype "passive"))
      (node (ref "U$2") (pin "3") (pinfunction "3/CAN-TX/PWM_3") (pintype "bidirectional"))
    )
    (net (code "48") (name "T3") (class "Default")
      (node (ref "R6") (pin "2") (pinfunction "2_2") (pintype "passive"))
      (node (ref "U$2") (pin "4") (pinfunction "4/CAN-RX-PWM_4") (pintype "bidirectional"))
    )
    (net (code "49") (name "T4") (class "Default")
      (node (ref "R8") (pin "2") (pinfunction "2_2") (pintype "passive"))
      (node (ref "U$2") (pin "5") (pinfunction "5/PWM_5") (pintype "bidirectional"))
    )
    (net (code "50") (name "T5") (class "Default")
      (node (ref "R10") (pin "2") (pinfunction "2_2") (pintype "passive"))
      (node (ref "U$2") (pin "6") (pinfunction "6/PWM_6") (pintype "bidirectional"))
    )
    (net (code "51") (name "T6") (class "Default")
      (node (ref "R12") (pin "2") (pinfunction "2_2") (pintype "passive"))
      (node (ref "U$2") (pin "7") (pinfunction "7/RX3_7") (pintype "bidirectional"))
    )
    (net (code "52") (name "T7") (class "Default")
      (node (ref "R14") (pin "2") (pinfunction "2_2") (pintype "passive"))
      (node (ref "U$2") (pin "8") (pinfunction "8/TX3_8") (pintype "bidirectional"))
    )
    (net (code "53") (name "T8") (class "Default")
      (node (ref "R16") (pin "2") (pinfunction "2_2") (pintype "passive"))
      (node (ref "U$2") (pin "9") (pinfunction "9/RX2/PWM_9") (pintype "bidirectional"))
    )
    (net (code "54") (name "T9") (class "Default")
      (node (ref "R18") (pin "2") (pinfunction "2_2") (pintype "passive"))
      (node (ref "U$2") (pin "10") (pinfunction "10/TX2/PWM_10") (pintype "bidirectional"))
    )
    (net (code "55") (name "T10") (class "Default")
      (node (ref "R20") (pin "2") (pinfunction "2_2") (pintype "passive"))
      (node (ref "U$2") (pin "11") (pinfunction "11/MOSI_11") (pintype "bidirectional"))
    )
    (net (code "56") (name "T11") (class "Default")
      (node (ref "R22") (pin "2") (pinfunction "2_2") (pintype "passive"))
      (node (ref "U$2") (pin "12") (pinfunction "12/MISO_12") (pintype "bidirectional"))
    )
    (net (code "57") (name "T12") (class "Default")
      (node (ref "R24") (pin "2") (pinfunction "2_2") (pintype "passive"))
      (node (ref "U$2") (pin "13") (pinfunction "13/SCK/LED_13") (pintype "bidirectional"))
    )
    (net (code "58") (name "TRS_MIDI") (class "Default")
      (node (ref "U$2") (pin "21/A7") (pinfunction "21/A7/PWM_21/A7") (pintype "bidirectional"))
      (node (ref "U$3") (pin "5") (pinfunction "VO_5") (pintype "passive"))
    )
    (net (code "59") (name "unconnected-(CV-IN-SWITCH-PadP$2_SWITCH)") (class "Default")
      (node (ref "CV-IN") (pin "P$2_SWITCH") (pinfunction "SWITCH_P$2_SWITCH") (pintype "passive"))
    )
    (net (code "60") (name "unconnected-(GI1-SWITCH-PadP$2_SWITCH)") (class "Default")
      (node (ref "GI1") (pin "P$2_SWITCH") (pinfunction "SWITCH_P$2_SWITCH") (pintype "passive"))
    )
    (net (code "61") (name "unconnected-(U$2-0{slash}RX1{slash}T-Pad0)") (class "Default")
      (node (ref "U$2") (pin "0") (pinfunction "0/RX1/T_0") (pintype "bidirectional"))
    )
    (net (code "62") (name "unconnected-(U$2-1{slash}TX1{slash}T-Pad1)") (class "Default")
      (node (ref "U$2") (pin "1") (pinfunction "1/TX1/T_1") (pintype "bidirectional"))
    )
    (net (code "63") (name "unconnected-(U$2-20{slash}A6{slash}PWM-Pad20{slash}A6)") (class "Default")
      (node (ref "U$2") (pin "20/A6") (pinfunction "20/A6/PWM_20/A6") (pintype "bidirectional"))
    )
    (net (code "64") (name "unconnected-(U$2-23{slash}A9{slash}T{slash}PWM-Pad23{slash}A9)") (class "Default")
      (node (ref "U$2") (pin "23/A9") (pinfunction "23/A9/T/PWM_23/A9") (pintype "bidirectional"))
    )
    (net (code "65") (name "unconnected-(U$2-A14{slash}DAC-PadRESET{slash}DAC)") (class "Default")
      (node (ref "U$2") (pin "RESET/DAC") (pinfunction "A14/DAC_RESET/DAC") (pintype "bidirectional"))
    )
    (net (code "66") (name "unconnected-(U2-PadNC)") (class "Default")
      (node (ref "U2") (pin "NC") (pinfunction "NC_NC") (pintype "passive"))
    )
  )
)
